# carrier.net
KiCad netlist of a schematic drawn in Altium Designer
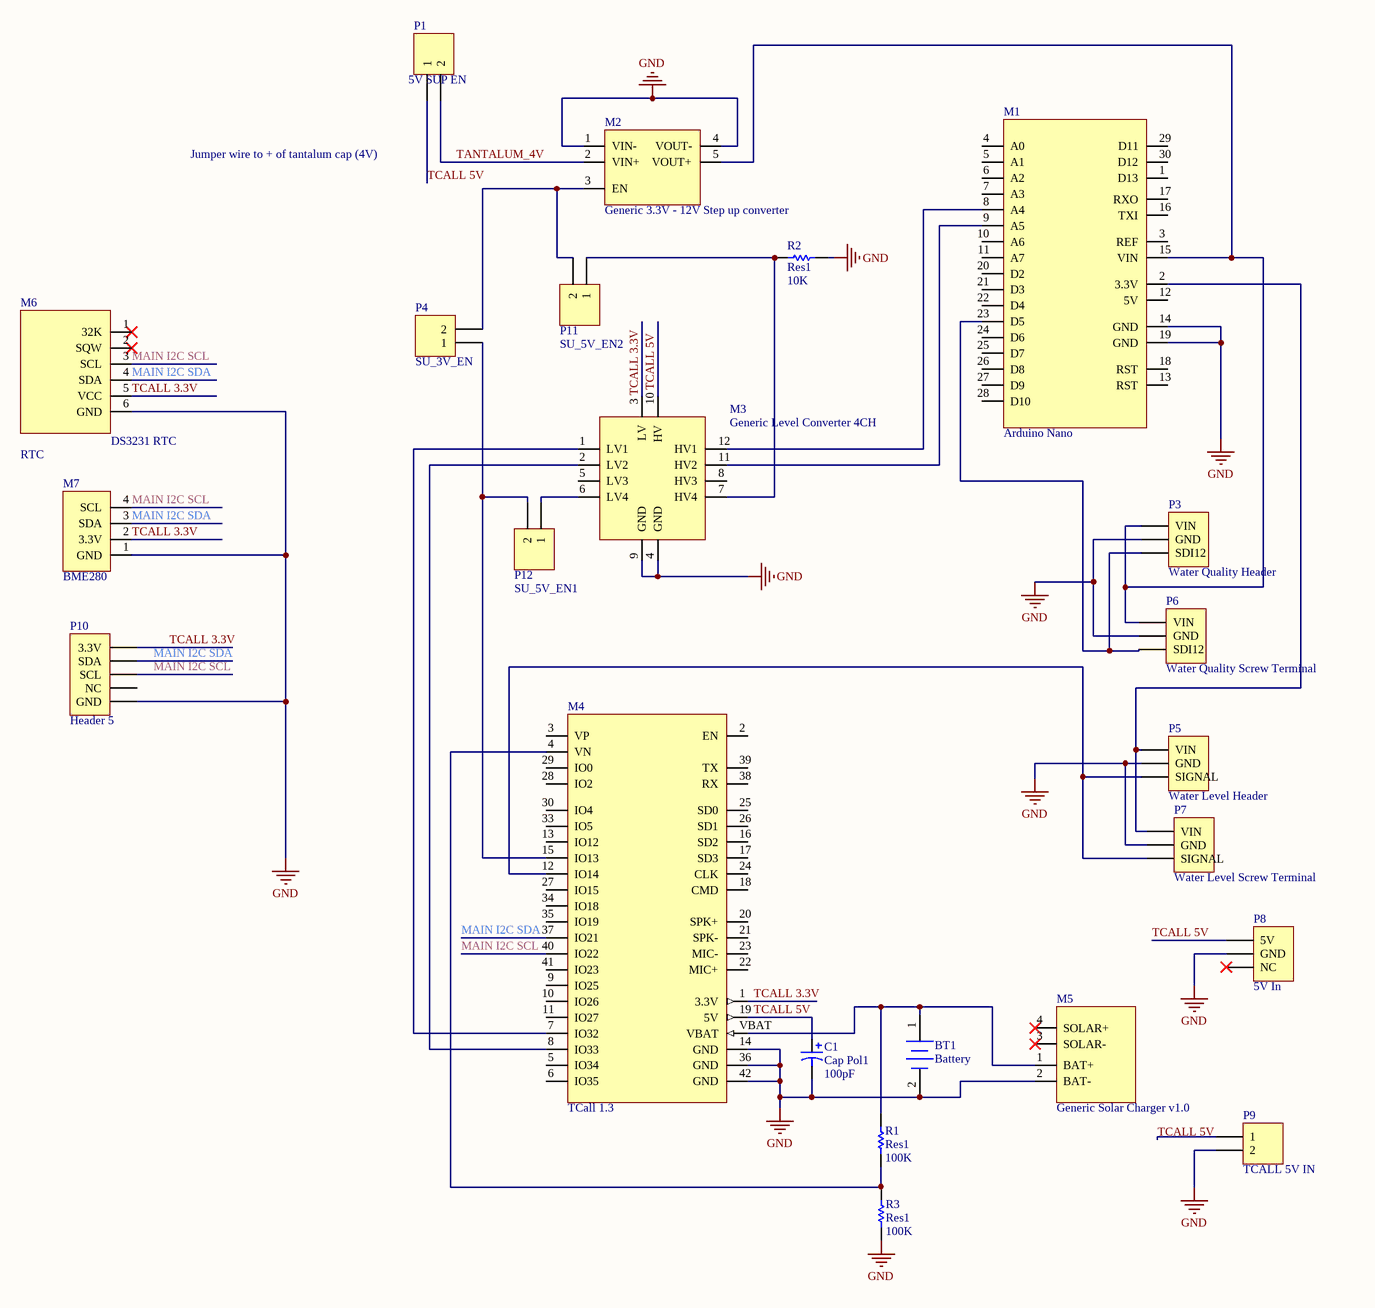
[diagram p0: carrier.SchDoc]

(export (version "E")
  (design (tool "Eeschema 10.0.6"))
  (components
    (comp (ref "BT1")
      (value "Battery")
      (footprint "BAT-2")
      (description "Multicell Battery")
      (fields (field (name "PUBLISHER") "Altium Limited"))
      (libsource (lib "Miscellaneous Devices") (part "Battery"))
    )
    (comp (ref "C1")
      (value "Cap Pol1")
      (footprint "RB7.6-15")
      (description "Polarized Capacitor (Radial)")
      (fields (field (name "ALTIUM_VALUE") "100pF") (field (name "PUBLISHER") "Altium Limited"))
      (libsource (lib "Miscellaneous Devices") (part "Cap Pol1"))
    )
    (comp (ref "M1")
      (value "Arduino Nano")
      (footprint "Arduino Nano")
      (libsource (lib "eliot") (part "Arduino Nano"))
    )
    (comp (ref "M2")
      (value "Generic 3.3V - 12V Step up converter")
      (footprint "Generic 3.3 - 12V step up")
      (libsource (lib "eliot") (part "Generic 3.3V - 12V Step up converter"))
    )
    (comp (ref "M3")
      (value "Generic Level Converter 4CH")
      (footprint "Generic Level Converter")
      (libsource (lib "eliot") (part "Generic Level Converter 4CH"))
    )
    (comp (ref "M4")
      (value "TCall 1.3")
      (footprint "TCALL V1.3")
      (libsource (lib "eliot") (part "TCall 1.3"))
    )
    (comp (ref "M5")
      (value "Generic Solar Charger v1.0")
      (footprint "Generic solar charger")
      (libsource (lib "eliot") (part "Generic Solar Charger v1.0"))
    )
    (comp (ref "M6")
      (value "RTC")
      (footprint "GENERIC RTC Module")
      (libsource (lib "eliot") (part "Generic RTC Module"))
    )
    (comp (ref "M7")
      (value "BME280")
      (footprint "Sparkfun BME280 Module")
      (libsource (lib "eliot") (part "Sparkfun BME280 Module"))
    )
    (comp (ref "P1")
      (value "5V SUP EN")
      (footprint "HDR1X2")
      (description "Header, 2-Pin")
      (fields (field (name "PUBLISHER") "Altium Limited"))
      (libsource (lib "Miscellaneous Connectors") (part "Header 2"))
    )
    (comp (ref "P3")
      (value "Water Quality Header")
      (footprint "HDR1X3")
      (description "Water Ql.")
      (fields (field (name "PUBLISHER") "Altium Limited"))
      (libsource (lib "") (part "Header 3_1"))
    )
    (comp (ref "P4")
      (value "SU_3V_EN")
      (footprint "HDR1X2")
      (description "Header, 2-Pin")
      (fields (field (name "PUBLISHER") "Altium Limited"))
      (libsource (lib "") (part "Header 2_1"))
    )
    (comp (ref "P5")
      (value "Water Level Header")
      (footprint "HDR1X3")
      (description "Header, 3-Pin")
      (fields (field (name "PUBLISHER") "Altium Limited"))
      (libsource (lib "Miscellaneous Connectors") (part "Header 3"))
    )
    (comp (ref "P6")
      (value "Water Quality Screw Terminal")
      (footprint "Terminal Block 3w 5mm")
      (description "Header, 3-Pin")
      (fields (field (name "PUBLISHER") "Altium Limited"))
      (libsource (lib "") (part "Header 3_1"))
    )
    (comp (ref "P7")
      (value "Water Level Screw Terminal")
      (footprint "Terminal Block 3w 5mm")
      (description "Header, 3-Pin")
      (fields (field (name "PUBLISHER") "Altium Limited"))
      (libsource (lib "Miscellaneous Connectors") (part "Header 3"))
    )
    (comp (ref "P8")
      (value "5V In")
      (footprint "Terminal Block 3w 5mm")
      (description "Header, 3-Pin")
      (fields (field (name "PUBLISHER") "Altium Limited"))
      (libsource (lib "") (part "Header 3_2"))
    )
    (comp (ref "P9")
      (value "TCALL 5V IN")
      (footprint "HDR1X2")
      (description "Header, 2-Pin")
      (fields (field (name "PUBLISHER") "Altium Limited"))
      (libsource (lib "") (part "Header 2_2"))
    )
    (comp (ref "P10")
      (value "Header 5")
      (footprint "HDR1X5")
      (description "Header, 5-Pin")
      (fields (field (name "PUBLISHER") "Altium Limited"))
      (libsource (lib "Miscellaneous Connectors") (part "Header 5"))
    )
    (comp (ref "P11")
      (value "SU_5V_EN2")
      (footprint "HDR1X2")
      (description "Header, 2-Pin")
      (fields (field (name "PUBLISHER") "Altium Limited"))
      (libsource (lib "") (part "Header 2_3"))
    )
    (comp (ref "P12")
      (value "SU_5V_EN1")
      (footprint "HDR1X2")
      (description "Header, 2-Pin")
      (fields (field (name "PUBLISHER") "Altium Limited"))
      (libsource (lib "") (part "Header 2_3"))
    )
    (comp (ref "R1")
      (value "Res1")
      (footprint "AXIAL-0.3")
      (description "Resistor")
      (fields (field (name "ALTIUM_VALUE") "100K") (field (name "PUBLISHER") "Altium Limited"))
      (libsource (lib "Miscellaneous Devices") (part "Res1"))
    )
    (comp (ref "R2")
      (value "Res1")
      (footprint "AXIAL-0.3")
      (description "Resistor")
      (fields (field (name "ALTIUM_VALUE") "10K") (field (name "PUBLISHER") "Altium Limited"))
      (libsource (lib "Miscellaneous Devices") (part "Res1"))
    )
    (comp (ref "R3")
      (value "Res1")
      (footprint "AXIAL-0.3")
      (description "Resistor")
      (fields (field (name "ALTIUM_VALUE") "100K") (field (name "PUBLISHER") "Altium Limited"))
      (libsource (lib "Miscellaneous Devices") (part "Res1"))
    )
  )
  (nets
    (net (code "1") (name "/MAIN I2C SCL") (class "Default")
      (node (ref "M4") (pin "40") (pinfunction "IO22_40") (pintype "passive"))
      (node (ref "M6") (pin "3") (pinfunction "SCL_3") (pintype "passive"))
      (node (ref "M7") (pin "4") (pinfunction "SCL_4") (pintype "passive"))
      (node (ref "P10") (pin "3") (pinfunction "SCL_3") (pintype "passive"))
    )
    (net (code "2") (name "/MAIN I2C SDA") (class "Default")
      (node (ref "M4") (pin "37") (pinfunction "IO21_37") (pintype "passive"))
      (node (ref "M6") (pin "4") (pinfunction "SDA_4") (pintype "passive"))
      (node (ref "M7") (pin "3") (pinfunction "SDA_3") (pintype "passive"))
      (node (ref "P10") (pin "2") (pinfunction "SDA_2") (pintype "passive"))
    )
    (net (code "3") (name "/TANTALUM_4V") (class "Default")
      (node (ref "M2") (pin "2") (pinfunction "VIN+_2") (pintype "passive"))
      (node (ref "P1") (pin "2") (pinfunction "2_2") (pintype "passive"))
    )
    (net (code "4") (name "/TCALL 3.3V") (class "Default")
      (node (ref "M3") (pin "3") (pinfunction "LV_3") (pintype "passive"))
      (node (ref "M4") (pin "1") (pinfunction "3.3V_1") (pintype "output"))
      (node (ref "M6") (pin "5") (pinfunction "VCC_5") (pintype "passive"))
      (node (ref "M7") (pin "2") (pinfunction "3.3V_2") (pintype "passive"))
      (node (ref "P10") (pin "1") (pinfunction "3.3V_1") (pintype "passive"))
    )
    (net (code "5") (name "/TCALL 5V") (class "Default")
      (node (ref "C1") (pin "1") (pinfunction "1_1") (pintype "passive"))
      (node (ref "M3") (pin "10") (pinfunction "HV_10") (pintype "passive"))
      (node (ref "M4") (pin "19") (pinfunction "5V_19") (pintype "output"))
      (node (ref "P1") (pin "1") (pinfunction "1_1") (pintype "passive"))
      (node (ref "P8") (pin "1") (pinfunction "5V_1") (pintype "passive"))
      (node (ref "P9") (pin "1") (pinfunction "1_1") (pintype "passive"))
    )
    (net (code "6") (name "GND") (class "Default")
      (node (ref "BT1") (pin "2") (pinfunction "-_2") (pintype "passive"))
      (node (ref "C1") (pin "2") (pinfunction "2_2") (pintype "passive"))
      (node (ref "M1") (pin "14") (pinfunction "GND_14") (pintype "passive"))
      (node (ref "M1") (pin "19") (pinfunction "GND_19") (pintype "passive"))
      (node (ref "M2") (pin "1") (pinfunction "VIN-_1") (pintype "passive"))
      (node (ref "M2") (pin "4") (pinfunction "VOUT-_4") (pintype "passive"))
      (node (ref "M3") (pin "4") (pinfunction "GND_4") (pintype "passive"))
      (node (ref "M3") (pin "9") (pinfunction "GND_9") (pintype "passive"))
      (node (ref "M4") (pin "14") (pinfunction "GND_14") (pintype "passive"))
      (node (ref "M4") (pin "36") (pinfunction "GND_36") (pintype "passive"))
      (node (ref "M4") (pin "42") (pinfunction "GND_42") (pintype "passive"))
      (node (ref "M5") (pin "2") (pinfunction "BAT-_2") (pintype "passive"))
      (node (ref "M6") (pin "6") (pinfunction "GND_6") (pintype "passive"))
      (node (ref "M7") (pin "1") (pinfunction "GND_1") (pintype "passive"))
      (node (ref "P10") (pin "5") (pinfunction "GND_5") (pintype "passive"))
      (node (ref "P3") (pin "2") (pinfunction "GND_2") (pintype "passive"))
      (node (ref "P5") (pin "2") (pinfunction "GND_2") (pintype "passive"))
      (node (ref "P6") (pin "2") (pinfunction "GND_2") (pintype "passive"))
      (node (ref "P7") (pin "2") (pinfunction "GND_2") (pintype "passive"))
      (node (ref "P8") (pin "2") (pinfunction "GND_2") (pintype "passive"))
      (node (ref "P9") (pin "2") (pinfunction "2_2") (pintype "passive"))
      (node (ref "R2") (pin "1") (pinfunction "1_1") (pintype "passive"))
      (node (ref "R3") (pin "1") (pinfunction "1_1") (pintype "passive"))
    )
    (net (code "7") (name "Net-(BT1-+)") (class "Default")
      (node (ref "BT1") (pin "1") (pinfunction "+_1") (pintype "passive"))
      (node (ref "M4") (pin "VBAT") (pinfunction "VBAT_VBAT") (pintype "input"))
      (node (ref "M5") (pin "1") (pinfunction "BAT+_1") (pintype "passive"))
      (node (ref "R1") (pin "2") (pinfunction "2_2") (pintype "passive"))
    )
    (net (code "8") (name "Net-(M1-3.3V)") (class "Default")
      (node (ref "M1") (pin "2") (pinfunction "3.3V_2") (pintype "passive"))
      (node (ref "P5") (pin "1") (pinfunction "VIN_1") (pintype "passive"))
      (node (ref "P7") (pin "1") (pinfunction "VIN_1") (pintype "passive"))
    )
    (net (code "9") (name "Net-(M1-A4)") (class "Default")
      (node (ref "M1") (pin "8") (pinfunction "A4_8") (pintype "passive"))
      (node (ref "M3") (pin "12") (pinfunction "HV1_12") (pintype "passive"))
    )
    (net (code "10") (name "Net-(M1-A5)") (class "Default")
      (node (ref "M1") (pin "9") (pinfunction "A5_9") (pintype "passive"))
      (node (ref "M3") (pin "11") (pinfunction "HV2_11") (pintype "passive"))
    )
    (net (code "11") (name "Net-(M1-D5)") (class "Default")
      (node (ref "M1") (pin "23") (pinfunction "D5_23") (pintype "passive"))
      (node (ref "P3") (pin "3") (pinfunction "SDI12_3") (pintype "passive"))
      (node (ref "P6") (pin "3") (pinfunction "SDI12_3") (pintype "passive"))
    )
    (net (code "12") (name "Net-(M1-VIN)") (class "Default")
      (node (ref "M1") (pin "15") (pinfunction "VIN_15") (pintype "passive"))
      (node (ref "M2") (pin "5") (pinfunction "VOUT+_5") (pintype "passive"))
      (node (ref "P3") (pin "1") (pinfunction "VIN_1") (pintype "passive"))
      (node (ref "P6") (pin "1") (pinfunction "VIN_1") (pintype "passive"))
    )
    (net (code "13") (name "Net-(M2-EN)") (class "Default")
      (node (ref "M2") (pin "3") (pinfunction "EN_3") (pintype "passive"))
      (node (ref "P11") (pin "2") (pinfunction "2_2") (pintype "passive"))
      (node (ref "P4") (pin "2") (pinfunction "2_2") (pintype "passive"))
    )
    (net (code "14") (name "Net-(M3-HV4)") (class "Default")
      (node (ref "M3") (pin "7") (pinfunction "HV4_7") (pintype "passive"))
      (node (ref "P11") (pin "1") (pinfunction "1_1") (pintype "passive"))
      (node (ref "R2") (pin "2") (pinfunction "2_2") (pintype "passive"))
    )
    (net (code "15") (name "Net-(M3-LV1)") (class "Default")
      (node (ref "M3") (pin "1") (pinfunction "LV1_1") (pintype "passive"))
      (node (ref "M4") (pin "7") (pinfunction "IO32_7") (pintype "passive"))
    )
    (net (code "16") (name "Net-(M3-LV2)") (class "Default")
      (node (ref "M3") (pin "2") (pinfunction "LV2_2") (pintype "passive"))
      (node (ref "M4") (pin "8") (pinfunction "IO33_8") (pintype "passive"))
    )
    (net (code "17") (name "Net-(M3-LV4)") (class "Default")
      (node (ref "M3") (pin "6") (pinfunction "LV4_6") (pintype "passive"))
      (node (ref "P12") (pin "1") (pinfunction "1_1") (pintype "passive"))
    )
    (net (code "18") (name "Net-(M4-IO13)") (class "Default")
      (node (ref "M4") (pin "15") (pinfunction "IO13_15") (pintype "passive"))
      (node (ref "P12") (pin "2") (pinfunction "2_2") (pintype "passive"))
      (node (ref "P4") (pin "1") (pinfunction "1_1") (pintype "passive"))
    )
    (net (code "19") (name "Net-(M4-IO14)") (class "Default")
      (node (ref "M4") (pin "12") (pinfunction "IO14_12") (pintype "passive"))
      (node (ref "P5") (pin "3") (pinfunction "SIGNAL_3") (pintype "passive"))
      (node (ref "P7") (pin "3") (pinfunction "SIGNAL_3") (pintype "passive"))
    )
    (net (code "20") (name "Net-(M4-VN)") (class "Default")
      (node (ref "M4") (pin "4") (pinfunction "VN_4") (pintype "passive"))
      (node (ref "R1") (pin "1") (pinfunction "1_1") (pintype "passive"))
      (node (ref "R3") (pin "2") (pinfunction "2_2") (pintype "passive"))
    )
    (net (code "21") (name "unconnected-(M1-5V-Pad12)") (class "Default")
      (node (ref "M1") (pin "12") (pinfunction "5V_12") (pintype "passive"))
    )
    (net (code "22") (name "unconnected-(M1-A0-Pad4)") (class "Default")
      (node (ref "M1") (pin "4") (pinfunction "A0_4") (pintype "passive"))
    )
    (net (code "23") (name "unconnected-(M1-A1-Pad5)") (class "Default")
      (node (ref "M1") (pin "5") (pinfunction "A1_5") (pintype "passive"))
    )
    (net (code "24") (name "unconnected-(M1-A2-Pad6)") (class "Default")
      (node (ref "M1") (pin "6") (pinfunction "A2_6") (pintype "passive"))
    )
    (net (code "25") (name "unconnected-(M1-A3-Pad7)") (class "Default")
      (node (ref "M1") (pin "7") (pinfunction "A3_7") (pintype "passive"))
    )
    (net (code "26") (name "unconnected-(M1-A6-Pad10)") (class "Default")
      (node (ref "M1") (pin "10") (pinfunction "A6_10") (pintype "passive"))
    )
    (net (code "27") (name "unconnected-(M1-A7-Pad11)") (class "Default")
      (node (ref "M1") (pin "11") (pinfunction "A7_11") (pintype "passive"))
    )
    (net (code "28") (name "unconnected-(M1-D2-Pad20)") (class "Default")
      (node (ref "M1") (pin "20") (pinfunction "D2_20") (pintype "passive"))
    )
    (net (code "29") (name "unconnected-(M1-D3-Pad21)") (class "Default")
      (node (ref "M1") (pin "21") (pinfunction "D3_21") (pintype "passive"))
    )
    (net (code "30") (name "unconnected-(M1-D4-Pad22)") (class "Default")
      (node (ref "M1") (pin "22") (pinfunction "D4_22") (pintype "passive"))
    )
    (net (code "31") (name "unconnected-(M1-D6-Pad24)") (class "Default")
      (node (ref "M1") (pin "24") (pinfunction "D6_24") (pintype "passive"))
    )
    (net (code "32") (name "unconnected-(M1-D7-Pad25)") (class "Default")
      (node (ref "M1") (pin "25") (pinfunction "D7_25") (pintype "passive"))
    )
    (net (code "33") (name "unconnected-(M1-D8-Pad26)") (class "Default")
      (node (ref "M1") (pin "26") (pinfunction "D8_26") (pintype "passive"))
    )
    (net (code "34") (name "unconnected-(M1-D9-Pad27)") (class "Default")
      (node (ref "M1") (pin "27") (pinfunction "D9_27") (pintype "passive"))
    )
    (net (code "35") (name "unconnected-(M1-D10-Pad28)") (class "Default")
      (node (ref "M1") (pin "28") (pinfunction "D10_28") (pintype "passive"))
    )
    (net (code "36") (name "unconnected-(M1-D11-Pad29)") (class "Default")
      (node (ref "M1") (pin "29") (pinfunction "D11_29") (pintype "passive"))
    )
    (net (code "37") (name "unconnected-(M1-D12-Pad30)") (class "Default")
      (node (ref "M1") (pin "30") (pinfunction "D12_30") (pintype "passive"))
    )
    (net (code "38") (name "unconnected-(M1-D13-Pad1)") (class "Default")
      (node (ref "M1") (pin "1") (pinfunction "D13_1") (pintype "passive"))
    )
    (net (code "39") (name "unconnected-(M1-REF-Pad3)") (class "Default")
      (node (ref "M1") (pin "3") (pinfunction "REF_3") (pintype "passive"))
    )
    (net (code "40") (name "unconnected-(M1-RST-Pad13)") (class "Default")
      (node (ref "M1") (pin "13") (pinfunction "RST_13") (pintype "passive"))
    )
    (net (code "41") (name "unconnected-(M1-RST-Pad18)") (class "Default")
      (node (ref "M1") (pin "18") (pinfunction "RST_18") (pintype "passive"))
    )
    (net (code "42") (name "unconnected-(M1-RXO-Pad17)") (class "Default")
      (node (ref "M1") (pin "17") (pinfunction "RXO_17") (pintype "passive"))
    )
    (net (code "43") (name "unconnected-(M1-TXI-Pad16)") (class "Default")
      (node (ref "M1") (pin "16") (pinfunction "TXI_16") (pintype "passive"))
    )
    (net (code "44") (name "unconnected-(M3-HV3-Pad8)") (class "Default")
      (node (ref "M3") (pin "8") (pinfunction "HV3_8") (pintype "passive"))
    )
    (net (code "45") (name "unconnected-(M3-LV3-Pad5)") (class "Default")
      (node (ref "M3") (pin "5") (pinfunction "LV3_5") (pintype "passive"))
    )
    (net (code "46") (name "unconnected-(M4-CLK-Pad24)") (class "Default")
      (node (ref "M4") (pin "24") (pinfunction "CLK_24") (pintype "passive"))
    )
    (net (code "47") (name "unconnected-(M4-CMD-Pad18)") (class "Default")
      (node (ref "M4") (pin "18") (pinfunction "CMD_18") (pintype "passive"))
    )
    (net (code "48") (name "unconnected-(M4-EN-Pad2)") (class "Default")
      (node (ref "M4") (pin "2") (pinfunction "EN_2") (pintype "passive"))
    )
    (net (code "49") (name "unconnected-(M4-IO0-Pad29)") (class "Default")
      (node (ref "M4") (pin "29") (pinfunction "IO0_29") (pintype "passive"))
    )
    (net (code "50") (name "unconnected-(M4-IO2-Pad28)") (class "Default")
      (node (ref "M4") (pin "28") (pinfunction "IO2_28") (pintype "passive"))
    )
    (net (code "51") (name "unconnected-(M4-IO4-Pad30)") (class "Default")
      (node (ref "M4") (pin "30") (pinfunction "IO4_30") (pintype "passive"))
    )
    (net (code "52") (name "unconnected-(M4-IO5-Pad33)") (class "Default")
      (node (ref "M4") (pin "33") (pinfunction "IO5_33") (pintype "passive"))
    )
    (net (code "53") (name "unconnected-(M4-IO12-Pad13)") (class "Default")
      (node (ref "M4") (pin "13") (pinfunction "IO12_13") (pintype "passive"))
    )
    (net (code "54") (name "unconnected-(M4-IO15-Pad27)") (class "Default")
      (node (ref "M4") (pin "27") (pinfunction "IO15_27") (pintype "passive"))
    )
    (net (code "55") (name "unconnected-(M4-IO18-Pad34)") (class "Default")
      (node (ref "M4") (pin "34") (pinfunction "IO18_34") (pintype "passive"))
    )
    (net (code "56") (name "unconnected-(M4-IO19-Pad35)") (class "Default")
      (node (ref "M4") (pin "35") (pinfunction "IO19_35") (pintype "passive"))
    )
    (net (code "57") (name "unconnected-(M4-IO23-Pad41)") (class "Default")
      (node (ref "M4") (pin "41") (pinfunction "IO23_41") (pintype "passive"))
    )
    (net (code "58") (name "unconnected-(M4-IO25-Pad9)") (class "Default")
      (node (ref "M4") (pin "9") (pinfunction "IO25_9") (pintype "passive"))
    )
    (net (code "59") (name "unconnected-(M4-IO26-Pad10)") (class "Default")
      (node (ref "M4") (pin "10") (pinfunction "IO26_10") (pintype "passive"))
    )
    (net (code "60") (name "unconnected-(M4-IO27-Pad11)") (class "Default")
      (node (ref "M4") (pin "11") (pinfunction "IO27_11") (pintype "passive"))
    )
    (net (code "61") (name "unconnected-(M4-IO34-Pad5)") (class "Default")
      (node (ref "M4") (pin "5") (pinfunction "IO34_5") (pintype "passive"))
    )
    (net (code "62") (name "unconnected-(M4-IO35-Pad6)") (class "Default")
      (node (ref "M4") (pin "6") (pinfunction "IO35_6") (pintype "passive"))
    )
    (net (code "63") (name "unconnected-(M4-MIC+-Pad22)") (class "Default")
      (node (ref "M4") (pin "22") (pinfunction "MIC+_22") (pintype "passive"))
    )
    (net (code "64") (name "unconnected-(M4-MIC--Pad23)") (class "Default")
      (node (ref "M4") (pin "23") (pinfunction "MIC-_23") (pintype "passive"))
    )
    (net (code "65") (name "unconnected-(M4-RX-Pad38)") (class "Default")
      (node (ref "M4") (pin "38") (pinfunction "RX_38") (pintype "passive"))
    )
    (net (code "66") (name "unconnected-(M4-SD0-Pad25)") (class "Default")
      (node (ref "M4") (pin "25") (pinfunction "SD0_25") (pintype "passive"))
    )
    (net (code "67") (name "unconnected-(M4-SD1-Pad26)") (class "Default")
      (node (ref "M4") (pin "26") (pinfunction "SD1_26") (pintype "passive"))
    )
    (net (code "68") (name "unconnected-(M4-SD2-Pad16)") (class "Default")
      (node (ref "M4") (pin "16") (pinfunction "SD2_16") (pintype "passive"))
    )
    (net (code "69") (name "unconnected-(M4-SD3-Pad17)") (class "Default")
      (node (ref "M4") (pin "17") (pinfunction "SD3_17") (pintype "passive"))
    )
    (net (code "70") (name "unconnected-(M4-SPK+-Pad20)") (class "Default")
      (node (ref "M4") (pin "20") (pinfunction "SPK+_20") (pintype "passive"))
    )
    (net (code "71") (name "unconnected-(M4-SPK--Pad21)") (class "Default")
      (node (ref "M4") (pin "21") (pinfunction "SPK-_21") (pintype "passive"))
    )
    (net (code "72") (name "unconnected-(M4-TX-Pad39)") (class "Default")
      (node (ref "M4") (pin "39") (pinfunction "TX_39") (pintype "passive"))
    )
    (net (code "73") (name "unconnected-(M4-VP-Pad3)") (class "Default")
      (node (ref "M4") (pin "3") (pinfunction "VP_3") (pintype "passive"))
    )
    (net (code "74") (name "unconnected-(M5-SOLAR+-Pad4)") (class "Default")
      (node (ref "M5") (pin "4") (pinfunction "SOLAR+_4") (pintype "passive+no_connect"))
    )
    (net (code "75") (name "unconnected-(M5-SOLAR--Pad3)") (class "Default")
      (node (ref "M5") (pin "3") (pinfunction "SOLAR-_3") (pintype "passive+no_connect"))
    )
    (net (code "76") (name "unconnected-(M6-32K-Pad1)") (class "Default")
      (node (ref "M6") (pin "1") (pinfunction "32K_1") (pintype "passive+no_connect"))
    )
    (net (code "77") (name "unconnected-(M6-SQW-Pad2)") (class "Default")
      (node (ref "M6") (pin "2") (pinfunction "SQW_2") (pintype "passive+no_connect"))
    )
    (net (code "78") (name "unconnected-(P8-NC-Pad3)") (class "Default")
      (node (ref "P8") (pin "3") (pinfunction "NC_3") (pintype "passive+no_connect"))
    )
    (net (code "79") (name "unconnected-(P10-NC-Pad4)") (class "Default")
      (node (ref "P10") (pin "4") (pinfunction "NC_4") (pintype "passive"))
    )
  )
)
